# AT89xx_Development_Kit.net
KiCad netlist of a schematic drawn in Altium Designer
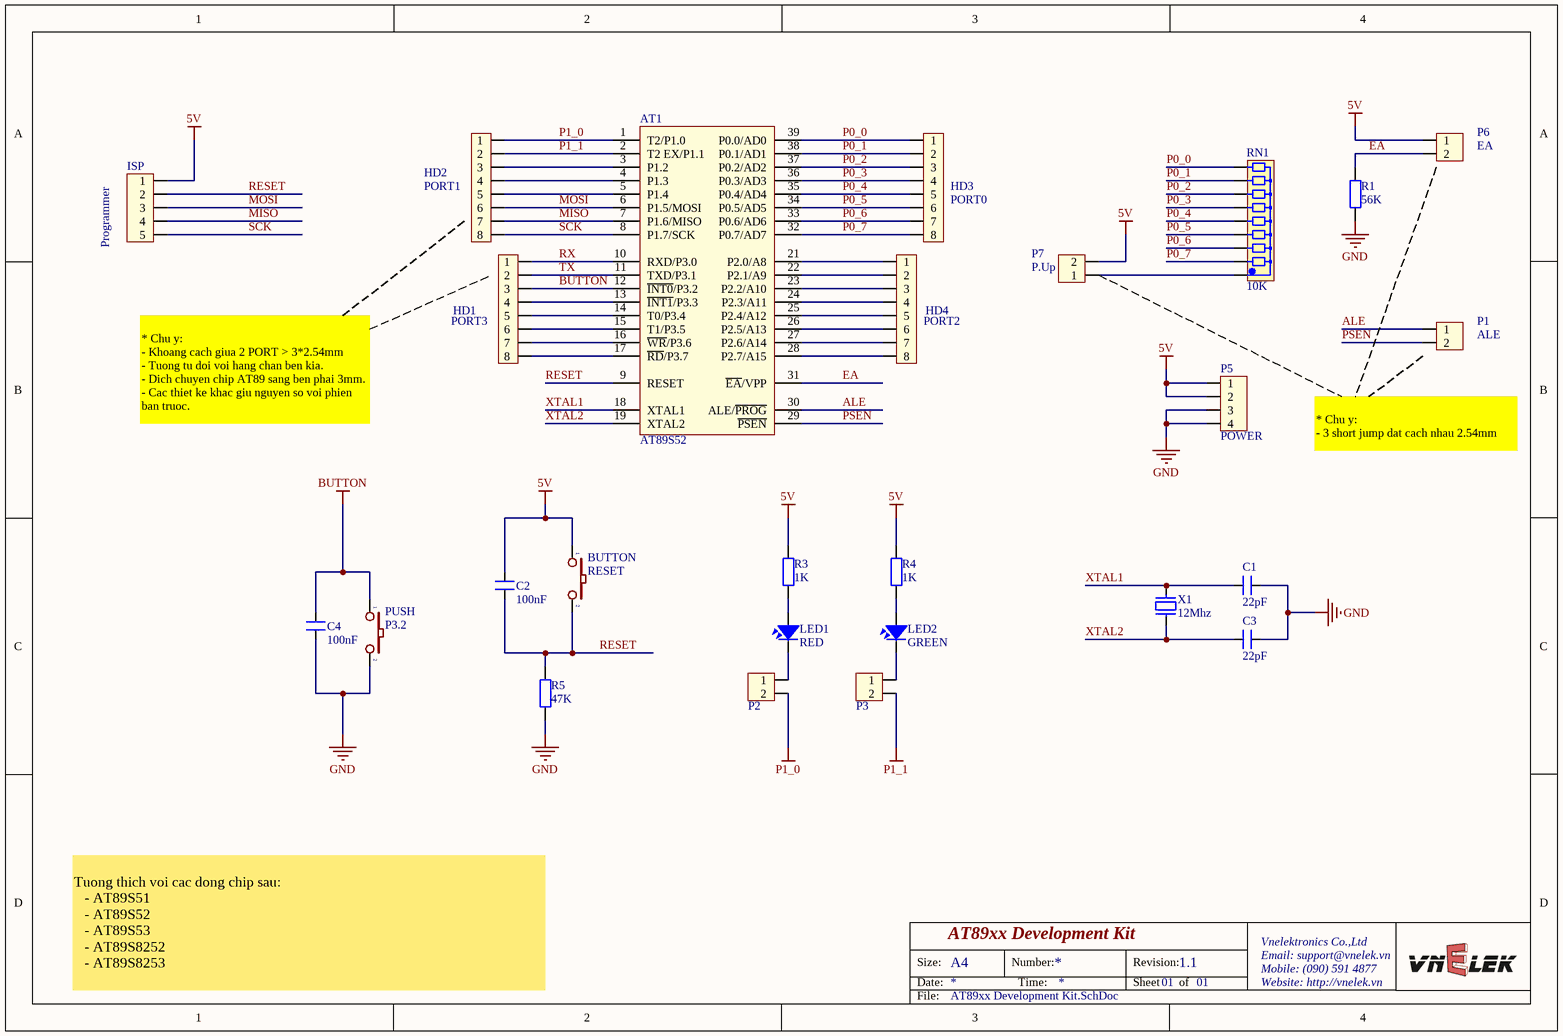
[diagram p0: AT89xx Development Kit.SchDoc]

(export (version "E")
  (design (tool "Eeschema 10.0.6"))
  (components
    (comp (ref "AT1")
      (value "AT89S52")
      (footprint "de gat xanh dip 40")
      (description "AT89S52, 8k Byte Flash Memory , 40 Pin")
      (libsource (lib "VNELEK") (part "AT89S52"))
    )
    (comp (ref "BUTTON")
      (value "RESET")
      (footprint "BUTTON 2PIN TRON")
      (description "Switch button 2 pin")
      (libsource (lib "VNELEK") (part "SW2"))
    )
    (comp (ref "C1")
      (value "22pF")
      (footprint "C0603")
      (description "Cap np  1pF - 472pF")
      (libsource (lib "syhaunguyen") (part "CN1"))
    )
    (comp (ref "C2")
      (value "100nF")
      (footprint "C0805")
      (description "Cap np  1pF - 472pF")
      (libsource (lib "syhaunguyen") (part "CN1"))
    )
    (comp (ref "C3")
      (value "22pF")
      (footprint "C0603")
      (description "Cap np  1pF - 472pF")
      (libsource (lib "syhaunguyen") (part "CN1"))
    )
    (comp (ref "C4")
      (value "100nF")
      (footprint "C0805")
      (description "Cap np  1pF - 472pF")
      (libsource (lib "syhaunguyen") (part "CN1"))
    )
    (comp (ref "HD1")
      (value "PORT3")
      (footprint "Header_8")
      (description "Hedear 8")
      (fields (field (name "CREAT BY") "VanDungEvn@Gmail.com"))
      (libsource (lib "syhaunguyen") (part "Hed8"))
    )
    (comp (ref "HD2")
      (value "PORT1")
      (footprint "Header_8")
      (description "Hedear 8")
      (fields (field (name "CREAT BY") "VanDungEvn@Gmail.com"))
      (libsource (lib "syhaunguyen") (part "Hed8"))
    )
    (comp (ref "HD3")
      (value "PORT0")
      (footprint "Header_8")
      (description "Hedear 8")
      (fields (field (name "CREAT BY") "VanDungEvn@Gmail.com"))
      (libsource (lib "") (part "Hed8_1"))
    )
    (comp (ref "HD4")
      (value "PORT2")
      (footprint "Header_8")
      (description "Hedear 8")
      (fields (field (name "CREAT BY") "VanDungEvn@Gmail.com"))
      (libsource (lib "") (part "Hed8_1"))
    )
    (comp (ref "ISP")
      (value "Programmer")
      (footprint "Header_5")
      (description "Header 5 (Green)")
      (libsource (lib "Tran Tuan") (part "Hed5"))
    )
    (comp (ref "LED1")
      (value "RED")
      (footprint "Led 0805R")
      (description "LED Single colour Green and Red")
      (libsource (lib "syhaunguyen") (part "LED"))
    )
    (comp (ref "LED2")
      (value "GREEN")
      (footprint "Led 0805G")
      (description "LED Single colour Green and Red")
      (libsource (lib "syhaunguyen") (part "LED"))
    )
    (comp (ref "P1")
      (value "ALE")
      (footprint "Header_2")
      (description "Header 2 (Green)")
      (libsource (lib "") (part "Hed2_1"))
    )
    (comp (ref "P2")
      (value "JUMP")
      (footprint "Header_2")
      (description "Header 2 (Green)")
      (libsource (lib "syhaunguyen") (part "Hed2"))
    )
    (comp (ref "P3")
      (value "JUMP")
      (footprint "Header_2")
      (description "Header 2 (Green)")
      (libsource (lib "syhaunguyen") (part "Hed2"))
    )
    (comp (ref "P5")
      (value "POWER")
      (footprint "Header_4")
      (description "Connector 4")
      (libsource (lib "lpson") (part "Con4"))
    )
    (comp (ref "P6")
      (value "EA")
      (footprint "Header_2")
      (description "Header 2 (Green)")
      (libsource (lib "") (part "Hed2_1"))
    )
    (comp (ref "P7")
      (value "P.Up")
      (footprint "Header_2")
      (description "Header 2 (Green)")
      (libsource (lib "") (part "Hed2_2"))
    )
    (comp (ref "PUSH")
      (value "P3.2")
      (footprint "BUTTON 2PIN TRON")
      (description "Switch button 2 pin")
      (libsource (lib "VNELEK") (part "SW2"))
    )
    (comp (ref "R1")
      (value "56K")
      (footprint "RESC2012(0805)")
      (description "Resistor")
      (fields (field (name "Comment") "Res2") (field (name "PUBLISHER") "Altium Limited"))
      (libsource (lib "Miscellaneous Devices") (part "Res2"))
    )
    (comp (ref "R3")
      (value "1K")
      (footprint "RESC2012(0805)")
      (description "Resistor")
      (fields (field (name "Comment") "Res2") (field (name "PUBLISHER") "Altium Limited"))
      (libsource (lib "") (part "Res2_1"))
    )
    (comp (ref "R4")
      (value "1K")
      (footprint "RESC2012(0805)")
      (description "Resistor")
      (fields (field (name "Comment") "Res2") (field (name "PUBLISHER") "Altium Limited"))
      (libsource (lib "") (part "Res2_1"))
    )
    (comp (ref "R5")
      (value "47K")
      (footprint "RESC2012(0805)")
      (description "Resistor")
      (fields (field (name "Comment") "Res2") (field (name "PUBLISHER") "Altium Limited"))
      (libsource (lib "Miscellaneous Devices") (part "Res2"))
    )
    (comp (ref "RN1")
      (value "10K")
      (footprint "RN8")
      (description "Resistor 8 (Thanh)")
      (libsource (lib "syhaunguyen") (part "RN8"))
    )
    (comp (ref "X1")
      (value "12Mhz")
      (footprint "CRYSTAL")
      (description "Crystal For all Crystal 2pin.")
      (libsource (lib "syhaunguyen") (part "XT2"))
    )
  )
  (nets
    (net (code "1") (name "/ALE") (class "Default")
      (node (ref "AT1") (pin "30") (pinfunction "ALE/~{PROG}_30") (pintype "passive"))
      (node (ref "P1") (pin "1") (pinfunction "1_1") (pintype "passive"))
    )
    (net (code "2") (name "/EA") (class "Default")
      (node (ref "AT1") (pin "31") (pinfunction "~{EA}/VPP_31") (pintype "passive"))
      (node (ref "P6") (pin "2") (pinfunction "2_2") (pintype "passive"))
      (node (ref "R1") (pin "1") (pinfunction "1_1") (pintype "passive"))
    )
    (net (code "3") (name "/MISO") (class "Default")
      (node (ref "AT1") (pin "7") (pinfunction "P1.6/MISO_7") (pintype "passive"))
      (node (ref "HD2") (pin "7") (pinfunction "7_7") (pintype "passive"))
      (node (ref "ISP") (pin "4") (pinfunction "4_4") (pintype "passive"))
    )
    (net (code "4") (name "/MOSI") (class "Default")
      (node (ref "AT1") (pin "6") (pinfunction "P1.5/MOSI_6") (pintype "passive"))
      (node (ref "HD2") (pin "6") (pinfunction "6_6") (pintype "passive"))
      (node (ref "ISP") (pin "3") (pinfunction "3_3") (pintype "passive"))
    )
    (net (code "5") (name "/P0_0") (class "Default")
      (node (ref "AT1") (pin "39") (pinfunction "P0.0/AD0_39") (pintype "passive"))
      (node (ref "HD3") (pin "1") (pinfunction "1_1") (pintype "passive"))
      (node (ref "RN1") (pin "9") (pinfunction "9_9") (pintype "passive"))
    )
    (net (code "6") (name "/P0_1") (class "Default")
      (node (ref "AT1") (pin "38") (pinfunction "P0.1/AD1_38") (pintype "passive"))
      (node (ref "HD3") (pin "2") (pinfunction "2_2") (pintype "passive"))
      (node (ref "RN1") (pin "8") (pinfunction "8_8") (pintype "passive"))
    )
    (net (code "7") (name "/P0_2") (class "Default")
      (node (ref "AT1") (pin "37") (pinfunction "P0.2/AD2_37") (pintype "passive"))
      (node (ref "HD3") (pin "3") (pinfunction "3_3") (pintype "passive"))
      (node (ref "RN1") (pin "7") (pinfunction "7_7") (pintype "passive"))
    )
    (net (code "8") (name "/P0_3") (class "Default")
      (node (ref "AT1") (pin "36") (pinfunction "P0.3/AD3_36") (pintype "passive"))
      (node (ref "HD3") (pin "4") (pinfunction "4_4") (pintype "passive"))
      (node (ref "RN1") (pin "6") (pinfunction "6_6") (pintype "passive"))
    )
    (net (code "9") (name "/P0_4") (class "Default")
      (node (ref "AT1") (pin "35") (pinfunction "P0.4/AD4_35") (pintype "passive"))
      (node (ref "HD3") (pin "5") (pinfunction "5_5") (pintype "passive"))
      (node (ref "RN1") (pin "5") (pinfunction "5_5") (pintype "passive"))
    )
    (net (code "10") (name "/P0_5") (class "Default")
      (node (ref "AT1") (pin "34") (pinfunction "P0.5/AD5_34") (pintype "passive"))
      (node (ref "HD3") (pin "6") (pinfunction "6_6") (pintype "passive"))
      (node (ref "RN1") (pin "4") (pinfunction "4_4") (pintype "passive"))
    )
    (net (code "11") (name "/P0_6") (class "Default")
      (node (ref "AT1") (pin "33") (pinfunction "P0.6/AD6_33") (pintype "passive"))
      (node (ref "HD3") (pin "7") (pinfunction "7_7") (pintype "passive"))
      (node (ref "RN1") (pin "3") (pinfunction "3_3") (pintype "passive"))
    )
    (net (code "12") (name "/P0_7") (class "Default")
      (node (ref "AT1") (pin "32") (pinfunction "P0.7/AD7_32") (pintype "passive"))
      (node (ref "HD3") (pin "8") (pinfunction "8_8") (pintype "passive"))
      (node (ref "RN1") (pin "2") (pinfunction "2_2") (pintype "passive"))
    )
    (net (code "13") (name "/PSEN") (class "Default")
      (node (ref "AT1") (pin "29") (pinfunction "~{PSEN}_29") (pintype "passive"))
      (node (ref "P1") (pin "2") (pinfunction "2_2") (pintype "passive"))
    )
    (net (code "14") (name "/RESET") (class "Default")
      (node (ref "AT1") (pin "9") (pinfunction "RESET_9") (pintype "passive"))
      (node (ref "BUTTON") (pin "2") (pinfunction "2_2") (pintype "passive"))
      (node (ref "C2") (pin "2") (pinfunction "2_2") (pintype "passive"))
      (node (ref "ISP") (pin "2") (pinfunction "2_2") (pintype "passive"))
      (node (ref "R5") (pin "1") (pinfunction "1_1") (pintype "passive"))
    )
    (net (code "15") (name "/RX") (class "Default")
      (node (ref "AT1") (pin "10") (pinfunction "RXD/P3.0_10") (pintype "passive"))
      (node (ref "HD1") (pin "1") (pinfunction "1_1") (pintype "passive"))
    )
    (net (code "16") (name "/SCK") (class "Default")
      (node (ref "AT1") (pin "8") (pinfunction "P1.7/SCK_8") (pintype "passive"))
      (node (ref "HD2") (pin "8") (pinfunction "8_8") (pintype "passive"))
      (node (ref "ISP") (pin "5") (pinfunction "5_5") (pintype "passive"))
    )
    (net (code "17") (name "/TX") (class "Default")
      (node (ref "AT1") (pin "11") (pinfunction "TXD/P3.1_11") (pintype "passive"))
      (node (ref "HD1") (pin "2") (pinfunction "2_2") (pintype "passive"))
    )
    (net (code "18") (name "/XTAL1") (class "Default")
      (node (ref "AT1") (pin "18") (pinfunction "XTAL1_18") (pintype "passive"))
      (node (ref "C1") (pin "2") (pinfunction "2_2") (pintype "passive"))
      (node (ref "X1") (pin "1") (pinfunction "1_1") (pintype "passive"))
    )
    (net (code "19") (name "/XTAL2") (class "Default")
      (node (ref "AT1") (pin "19") (pinfunction "XTAL2_19") (pintype "passive"))
      (node (ref "C3") (pin "2") (pinfunction "2_2") (pintype "passive"))
      (node (ref "X1") (pin "2") (pinfunction "2_2") (pintype "passive"))
    )
    (net (code "20") (name "5V") (class "Default")
      (node (ref "AT1") (pin "40") (pinfunction "5V_40") (pintype "power_in"))
      (node (ref "BUTTON") (pin "1") (pinfunction "1_1") (pintype "passive"))
      (node (ref "C2") (pin "1") (pinfunction "1_1") (pintype "passive"))
      (node (ref "ISP") (pin "1") (pinfunction "1_1") (pintype "passive"))
      (node (ref "P5") (pin "1") (pinfunction "1_1") (pintype "passive"))
      (node (ref "P5") (pin "2") (pinfunction "2_2") (pintype "passive"))
      (node (ref "P6") (pin "1") (pinfunction "1_1") (pintype "passive"))
      (node (ref "P7") (pin "2") (pinfunction "2_2") (pintype "passive"))
      (node (ref "R3") (pin "2") (pinfunction "2_2") (pintype "passive"))
      (node (ref "R4") (pin "2") (pinfunction "2_2") (pintype "passive"))
    )
    (net (code "21") (name "BUTTON") (class "Default")
      (node (ref "AT1") (pin "12") (pinfunction "~{INT0}/P3.2_12") (pintype "passive"))
      (node (ref "C4") (pin "1") (pinfunction "1_1") (pintype "passive"))
      (node (ref "HD1") (pin "3") (pinfunction "3_3") (pintype "passive"))
      (node (ref "PUSH") (pin "1") (pinfunction "1_1") (pintype "passive"))
    )
    (net (code "22") (name "GND") (class "Default")
      (node (ref "AT1") (pin "20") (pinfunction "GND_20") (pintype "power_in"))
      (node (ref "C1") (pin "1") (pinfunction "1_1") (pintype "passive"))
      (node (ref "C3") (pin "1") (pinfunction "1_1") (pintype "passive"))
      (node (ref "C4") (pin "2") (pinfunction "2_2") (pintype "passive"))
      (node (ref "P5") (pin "3") (pinfunction "3_3") (pintype "passive"))
      (node (ref "P5") (pin "4") (pinfunction "4_4") (pintype "passive"))
      (node (ref "PUSH") (pin "2") (pinfunction "2_2") (pintype "passive"))
      (node (ref "R1") (pin "2") (pinfunction "2_2") (pintype "passive"))
      (node (ref "R5") (pin "2") (pinfunction "2_2") (pintype "passive"))
    )
    (net (code "23") (name "Net-(AT1-P1.2)") (class "Default")
      (node (ref "AT1") (pin "3") (pinfunction "P1.2_3") (pintype "passive"))
      (node (ref "HD2") (pin "3") (pinfunction "3_3") (pintype "passive"))
    )
    (net (code "24") (name "Net-(AT1-P1.3)") (class "Default")
      (node (ref "AT1") (pin "4") (pinfunction "P1.3_4") (pintype "passive"))
      (node (ref "HD2") (pin "4") (pinfunction "4_4") (pintype "passive"))
    )
    (net (code "25") (name "Net-(AT1-P1.4)") (class "Default")
      (node (ref "AT1") (pin "5") (pinfunction "P1.4_5") (pintype "passive"))
      (node (ref "HD2") (pin "5") (pinfunction "5_5") (pintype "passive"))
    )
    (net (code "26") (name "Net-(AT1-P2.0{slash}A8)") (class "Default")
      (node (ref "AT1") (pin "21") (pinfunction "P2.0/A8_21") (pintype "passive"))
      (node (ref "HD4") (pin "1") (pinfunction "1_1") (pintype "passive"))
    )
    (net (code "27") (name "Net-(AT1-P2.1{slash}A9)") (class "Default")
      (node (ref "AT1") (pin "22") (pinfunction "P2.1/A9_22") (pintype "passive"))
      (node (ref "HD4") (pin "2") (pinfunction "2_2") (pintype "passive"))
    )
    (net (code "28") (name "Net-(AT1-P2.2{slash}A10)") (class "Default")
      (node (ref "AT1") (pin "23") (pinfunction "P2.2/A10_23") (pintype "passive"))
      (node (ref "HD4") (pin "3") (pinfunction "3_3") (pintype "passive"))
    )
    (net (code "29") (name "Net-(AT1-P2.3{slash}A11)") (class "Default")
      (node (ref "AT1") (pin "24") (pinfunction "P2.3/A11_24") (pintype "passive"))
      (node (ref "HD4") (pin "4") (pinfunction "4_4") (pintype "passive"))
    )
    (net (code "30") (name "Net-(AT1-P2.4{slash}A12)") (class "Default")
      (node (ref "AT1") (pin "25") (pinfunction "P2.4/A12_25") (pintype "passive"))
      (node (ref "HD4") (pin "5") (pinfunction "5_5") (pintype "passive"))
    )
    (net (code "31") (name "Net-(AT1-P2.5{slash}A13)") (class "Default")
      (node (ref "AT1") (pin "26") (pinfunction "P2.5/A13_26") (pintype "passive"))
      (node (ref "HD4") (pin "6") (pinfunction "6_6") (pintype "passive"))
    )
    (net (code "32") (name "Net-(AT1-P2.6{slash}A14)") (class "Default")
      (node (ref "AT1") (pin "27") (pinfunction "P2.6/A14_27") (pintype "passive"))
      (node (ref "HD4") (pin "7") (pinfunction "7_7") (pintype "passive"))
    )
    (net (code "33") (name "Net-(AT1-P2.7{slash}A15)") (class "Default")
      (node (ref "AT1") (pin "28") (pinfunction "P2.7/A15_28") (pintype "passive"))
      (node (ref "HD4") (pin "8") (pinfunction "8_8") (pintype "passive"))
    )
    (net (code "34") (name "Net-(AT1-T0{slash}P3.4)") (class "Default")
      (node (ref "AT1") (pin "14") (pinfunction "T0/P3.4_14") (pintype "passive"))
      (node (ref "HD1") (pin "5") (pinfunction "5_5") (pintype "passive"))
    )
    (net (code "35") (name "Net-(AT1-T1{slash}P3.5)") (class "Default")
      (node (ref "AT1") (pin "15") (pinfunction "T1/P3.5_15") (pintype "passive"))
      (node (ref "HD1") (pin "6") (pinfunction "6_6") (pintype "passive"))
    )
    (net (code "36") (name "Net-(AT1-~{INT1}{slash}P3.3)") (class "Default")
      (node (ref "AT1") (pin "13") (pinfunction "~{INT1}/P3.3_13") (pintype "passive"))
      (node (ref "HD1") (pin "4") (pinfunction "4_4") (pintype "passive"))
    )
    (net (code "37") (name "Net-(AT1-~{RD}{slash}P3.7)") (class "Default")
      (node (ref "AT1") (pin "17") (pinfunction "~{RD}/P3.7_17") (pintype "passive"))
      (node (ref "HD1") (pin "8") (pinfunction "8_8") (pintype "passive"))
    )
    (net (code "38") (name "Net-(AT1-~{WR}{slash}P3.6)") (class "Default")
      (node (ref "AT1") (pin "16") (pinfunction "~{WR}/P3.6_16") (pintype "passive"))
      (node (ref "HD1") (pin "7") (pinfunction "7_7") (pintype "passive"))
    )
    (net (code "39") (name "Net-(LED1-Pad1)") (class "Default")
      (node (ref "LED1") (pin "1") (pinfunction "1_1") (pintype "passive"))
      (node (ref "R3") (pin "1") (pinfunction "1_1") (pintype "passive"))
    )
    (net (code "40") (name "Net-(LED1-Pad2)") (class "Default")
      (node (ref "LED1") (pin "2") (pinfunction "2_2") (pintype "passive"))
      (node (ref "P2") (pin "1") (pinfunction "1_1") (pintype "passive"))
    )
    (net (code "41") (name "Net-(LED2-Pad1)") (class "Default")
      (node (ref "LED2") (pin "1") (pinfunction "1_1") (pintype "passive"))
      (node (ref "R4") (pin "1") (pinfunction "1_1") (pintype "passive"))
    )
    (net (code "42") (name "Net-(LED2-Pad2)") (class "Default")
      (node (ref "LED2") (pin "2") (pinfunction "2_2") (pintype "passive"))
      (node (ref "P3") (pin "1") (pinfunction "1_1") (pintype "passive"))
    )
    (net (code "43") (name "Net-(P7-Pad1)") (class "Default")
      (node (ref "P7") (pin "1") (pinfunction "1_1") (pintype "passive"))
      (node (ref "RN1") (pin "1") (pinfunction "1_1") (pintype "passive"))
    )
    (net (code "44") (name "P1_0") (class "Default")
      (node (ref "AT1") (pin "1") (pinfunction "T2/P1.0_1") (pintype "passive"))
      (node (ref "HD2") (pin "1") (pinfunction "1_1") (pintype "passive"))
      (node (ref "P2") (pin "2") (pinfunction "2_2") (pintype "passive"))
    )
    (net (code "45") (name "P1_1") (class "Default")
      (node (ref "AT1") (pin "2") (pinfunction "T2_EX/P1.1_2") (pintype "passive"))
      (node (ref "HD2") (pin "2") (pinfunction "2_2") (pintype "passive"))
      (node (ref "P3") (pin "2") (pinfunction "2_2") (pintype "passive"))
    )
  )
)
